# Image.net
KiCad netlist of a schematic drawn in Altium Designer
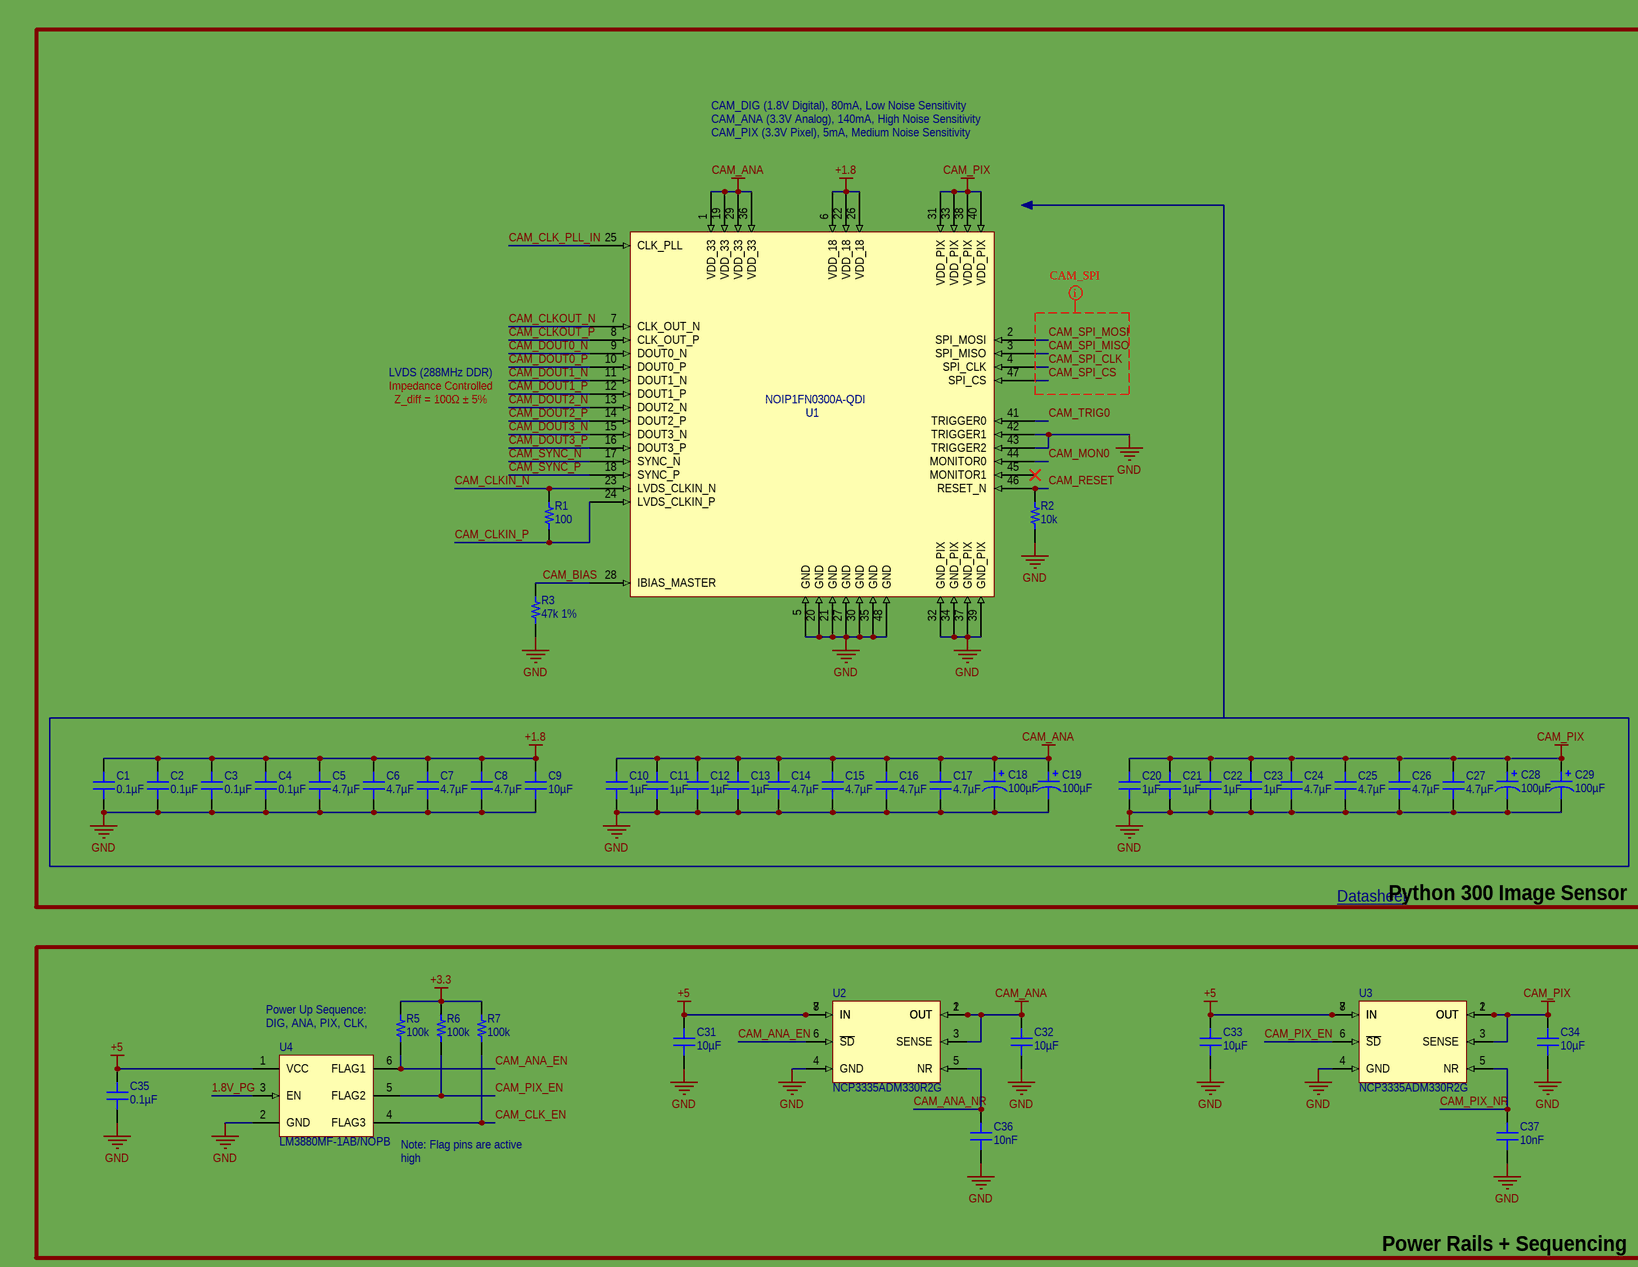
[diagram p0: Image.SchDoc, left]
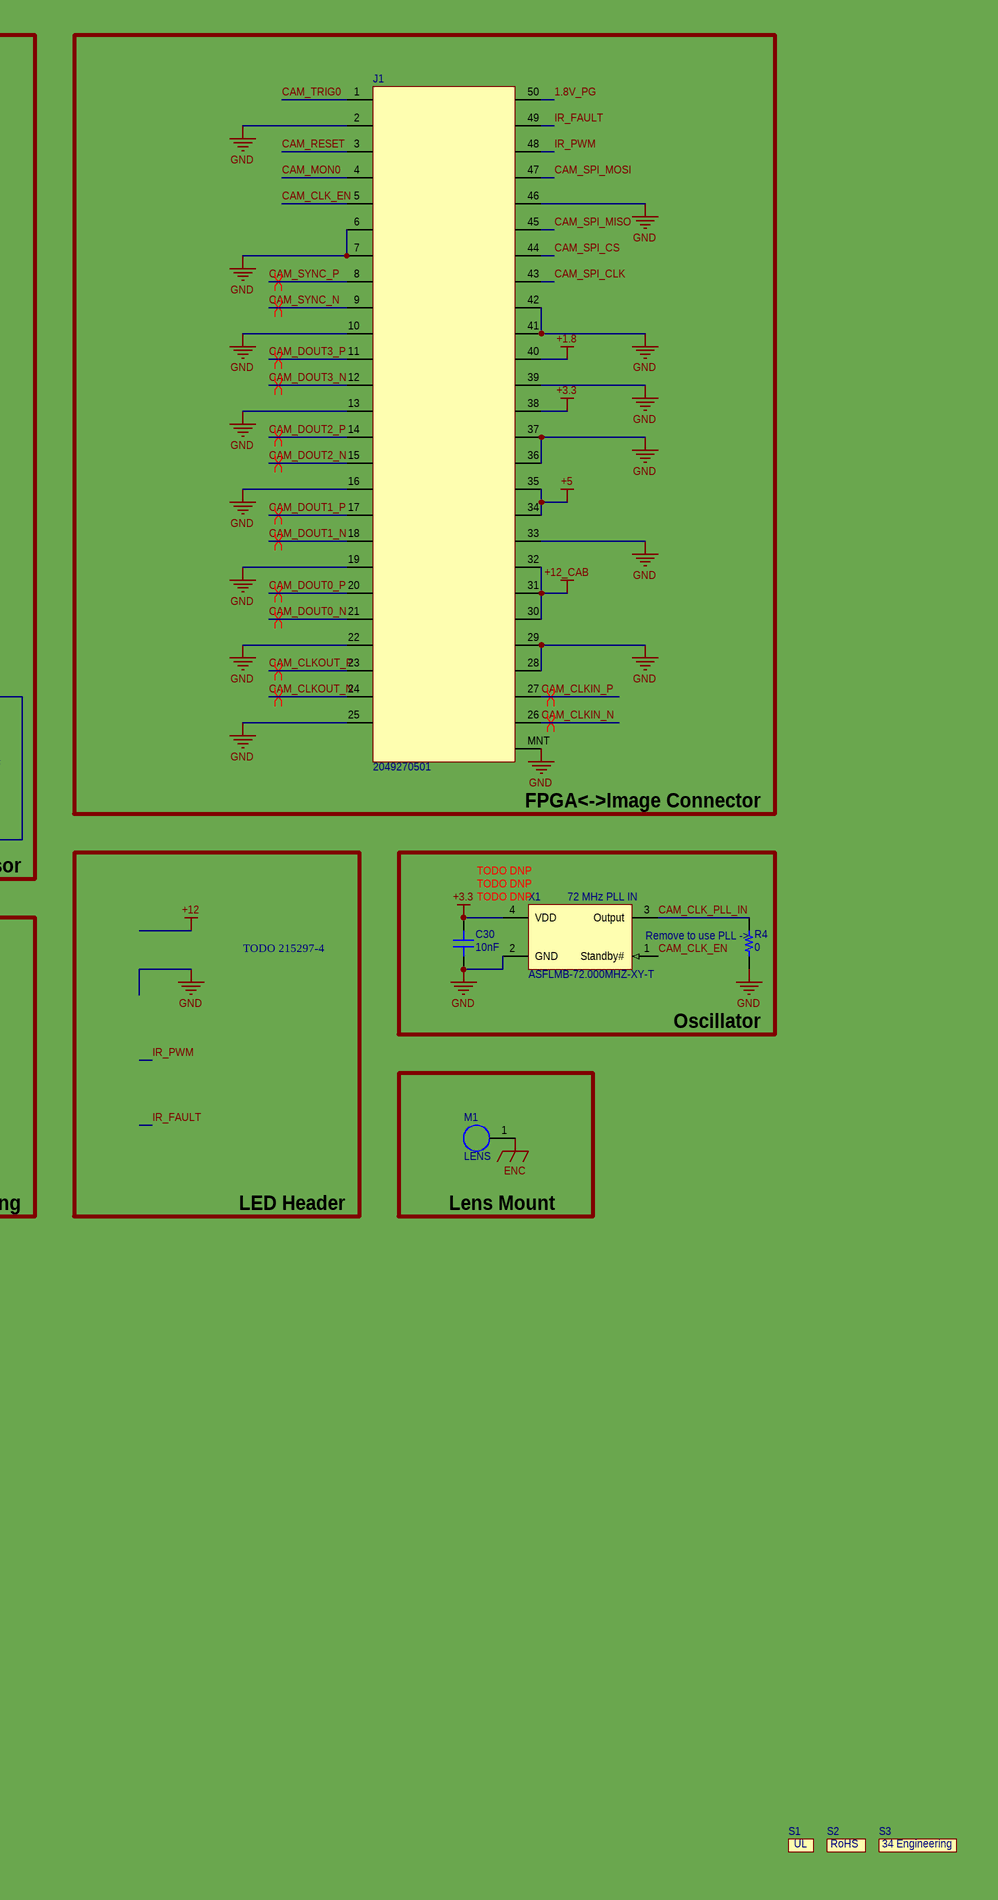
[diagram p1: Image.SchDoc, right]

(export (version "E")
  (design (tool "Eeschema 10.0.6"))
  (components
    (comp (ref "C1")
      (value "0.1µF")
      (footprint "CAP 0402_1005")
      (description "CAP CER 0.1UF 10V X7R 0402")
      (fields (field (name "PART NUMBER") "0402ZC104KAT2A") (field (name "MANUFACTURER") "AVX Corporation"))
      (libsource (lib "altium_library") (part "Capacitor"))
    )
    (comp (ref "C2")
      (value "0.1µF")
      (footprint "CAP 0402_1005")
      (description "CAP CER 0.1UF 10V X7R 0402")
      (fields (field (name "PART NUMBER") "0402ZC104KAT2A") (field (name "MANUFACTURER") "AVX Corporation"))
      (libsource (lib "altium_library") (part "Capacitor"))
    )
    (comp (ref "C3")
      (value "0.1µF")
      (footprint "CAP 0402_1005")
      (description "CAP CER 0.1UF 10V X7R 0402")
      (fields (field (name "PART NUMBER") "0402ZC104KAT2A") (field (name "MANUFACTURER") "AVX Corporation"))
      (libsource (lib "altium_library") (part "Capacitor"))
    )
    (comp (ref "C4")
      (value "0.1µF")
      (footprint "CAP 0402_1005")
      (description "CAP CER 0.1UF 10V X7R 0402")
      (fields (field (name "PART NUMBER") "0402ZC104KAT2A") (field (name "MANUFACTURER") "AVX Corporation"))
      (libsource (lib "altium_library") (part "Capacitor"))
    )
    (comp (ref "C5")
      (value "4.7µF")
      (footprint "CAP 0402_1005")
      (description "CAP CER 4.7UF 6.3V X5R 0402")
      (fields (field (name "PART NUMBER") "04026D475MAT2A") (field (name "MANUFACTURER") "AVX Corporation"))
      (libsource (lib "altium_library") (part "Capacitor"))
    )
    (comp (ref "C6")
      (value "4.7µF")
      (footprint "CAP 0402_1005")
      (description "CAP CER 4.7UF 6.3V X5R 0402")
      (fields (field (name "PART NUMBER") "04026D475MAT2A") (field (name "MANUFACTURER") "AVX Corporation"))
      (libsource (lib "altium_library") (part "Capacitor"))
    )
    (comp (ref "C7")
      (value "4.7µF")
      (footprint "CAP 0402_1005")
      (description "CAP CER 4.7UF 6.3V X5R 0402")
      (fields (field (name "PART NUMBER") "04026D475MAT2A") (field (name "MANUFACTURER") "AVX Corporation"))
      (libsource (lib "altium_library") (part "Capacitor"))
    )
    (comp (ref "C8")
      (value "4.7µF")
      (footprint "CAP 0402_1005")
      (description "CAP CER 4.7UF 6.3V X5R 0402")
      (fields (field (name "PART NUMBER") "04026D475MAT2A") (field (name "MANUFACTURER") "AVX Corporation"))
      (libsource (lib "altium_library") (part "Capacitor"))
    )
    (comp (ref "C9")
      (value "10µF")
      (footprint "CAP 0603_1608")
      (description "CAP CER 10UF 6.3V X5R 0603")
      (fields
        (field (name "PART NUMBER") "CL10A106MQ8NNNC")
        (field (name "MANUFACTURER") "Samsung Electro-Mechanics")
      )
      (libsource (lib "altium_library") (part "Capacitor"))
    )
    (comp (ref "C10")
      (value "1µF")
      (footprint "CAP 0402_1005")
      (description "CAP CER 1UF 6.3V X5R 0402")
      (fields (field (name "PART NUMBER") "C0402C105K9PAC7800") (field (name "MANUFACTURER") "KEMET"))
      (libsource (lib "altium_library") (part "Capacitor"))
    )
    (comp (ref "C11")
      (value "1µF")
      (footprint "CAP 0402_1005")
      (description "CAP CER 1UF 6.3V X5R 0402")
      (fields (field (name "PART NUMBER") "C0402C105K9PAC7800") (field (name "MANUFACTURER") "KEMET"))
      (libsource (lib "altium_library") (part "Capacitor"))
    )
    (comp (ref "C12")
      (value "1µF")
      (footprint "CAP 0402_1005")
      (description "CAP CER 1UF 6.3V X5R 0402")
      (fields (field (name "PART NUMBER") "C0402C105K9PAC7800") (field (name "MANUFACTURER") "KEMET"))
      (libsource (lib "altium_library") (part "Capacitor"))
    )
    (comp (ref "C13")
      (value "1µF")
      (footprint "CAP 0402_1005")
      (description "CAP CER 1UF 6.3V X5R 0402")
      (fields (field (name "PART NUMBER") "C0402C105K9PAC7800") (field (name "MANUFACTURER") "KEMET"))
      (libsource (lib "altium_library") (part "Capacitor"))
    )
    (comp (ref "C14")
      (value "4.7µF")
      (footprint "CAP 0402_1005")
      (description "CAP CER 4.7UF 6.3V X5R 0402")
      (fields (field (name "PART NUMBER") "04026D475MAT2A") (field (name "MANUFACTURER") "AVX Corporation"))
      (libsource (lib "altium_library") (part "Capacitor"))
    )
    (comp (ref "C15")
      (value "4.7µF")
      (footprint "CAP 0402_1005")
      (description "CAP CER 4.7UF 6.3V X5R 0402")
      (fields (field (name "PART NUMBER") "04026D475MAT2A") (field (name "MANUFACTURER") "AVX Corporation"))
      (libsource (lib "altium_library") (part "Capacitor"))
    )
    (comp (ref "C16")
      (value "4.7µF")
      (footprint "CAP 0402_1005")
      (description "CAP CER 4.7UF 6.3V X5R 0402")
      (fields (field (name "PART NUMBER") "04026D475MAT2A") (field (name "MANUFACTURER") "AVX Corporation"))
      (libsource (lib "altium_library") (part "Capacitor"))
    )
    (comp (ref "C17")
      (value "4.7µF")
      (footprint "CAP 0402_1005")
      (description "CAP CER 4.7UF 6.3V X5R 0402")
      (fields (field (name "PART NUMBER") "04026D475MAT2A") (field (name "MANUFACTURER") "AVX Corporation"))
      (libsource (lib "altium_library") (part "Capacitor"))
    )
    (comp (ref "C18")
      (value "100µF")
      (footprint "CAP POL 1411_3528")
      (description "CAP TANT 100UF 20% 10V 1411")
      (fields (field (name "PART NUMBER") "TPSB107M010R0400") (field (name "MANUFACTURER") "AVX Corporation"))
      (libsource (lib "altium_library") (part "Polarised Capacitor"))
    )
    (comp (ref "C19")
      (value "100µF")
      (footprint "CAP POL 1411_3528")
      (description "CAP TANT 100UF 20% 10V 1411")
      (fields (field (name "PART NUMBER") "TPSB107M010R0400") (field (name "MANUFACTURER") "AVX Corporation"))
      (libsource (lib "altium_library") (part "Polarised Capacitor"))
    )
    (comp (ref "C20")
      (value "1µF")
      (footprint "CAP 0402_1005")
      (description "CAP CER 1UF 6.3V X5R 0402")
      (fields (field (name "PART NUMBER") "C0402C105K9PAC7800") (field (name "MANUFACTURER") "KEMET"))
      (libsource (lib "altium_library") (part "Capacitor"))
    )
    (comp (ref "C21")
      (value "1µF")
      (footprint "CAP 0402_1005")
      (description "CAP CER 1UF 6.3V X5R 0402")
      (fields (field (name "PART NUMBER") "C0402C105K9PAC7800") (field (name "MANUFACTURER") "KEMET"))
      (libsource (lib "altium_library") (part "Capacitor"))
    )
    (comp (ref "C22")
      (value "1µF")
      (footprint "CAP 0402_1005")
      (description "CAP CER 1UF 6.3V X5R 0402")
      (fields (field (name "PART NUMBER") "C0402C105K9PAC7800") (field (name "MANUFACTURER") "KEMET"))
      (libsource (lib "altium_library") (part "Capacitor"))
    )
    (comp (ref "C23")
      (value "1µF")
      (footprint "CAP 0402_1005")
      (description "CAP CER 1UF 6.3V X5R 0402")
      (fields (field (name "PART NUMBER") "C0402C105K9PAC7800") (field (name "MANUFACTURER") "KEMET"))
      (libsource (lib "altium_library") (part "Capacitor"))
    )
    (comp (ref "C24")
      (value "4.7µF")
      (footprint "CAP 0402_1005")
      (description "CAP CER 4.7UF 6.3V X5R 0402")
      (fields (field (name "PART NUMBER") "04026D475MAT2A") (field (name "MANUFACTURER") "AVX Corporation"))
      (libsource (lib "altium_library") (part "Capacitor"))
    )
    (comp (ref "C25")
      (value "4.7µF")
      (footprint "CAP 0402_1005")
      (description "CAP CER 4.7UF 6.3V X5R 0402")
      (fields (field (name "PART NUMBER") "04026D475MAT2A") (field (name "MANUFACTURER") "AVX Corporation"))
      (libsource (lib "altium_library") (part "Capacitor"))
    )
    (comp (ref "C26")
      (value "4.7µF")
      (footprint "CAP 0402_1005")
      (description "CAP CER 4.7UF 6.3V X5R 0402")
      (fields (field (name "PART NUMBER") "04026D475MAT2A") (field (name "MANUFACTURER") "AVX Corporation"))
      (libsource (lib "altium_library") (part "Capacitor"))
    )
    (comp (ref "C27")
      (value "4.7µF")
      (footprint "CAP 0402_1005")
      (description "CAP CER 4.7UF 6.3V X5R 0402")
      (fields (field (name "PART NUMBER") "04026D475MAT2A") (field (name "MANUFACTURER") "AVX Corporation"))
      (libsource (lib "altium_library") (part "Capacitor"))
    )
    (comp (ref "C28")
      (value "100µF")
      (footprint "CAP POL 1411_3528")
      (description "CAP TANT 100UF 20% 10V 1411")
      (fields (field (name "PART NUMBER") "TPSB107M010R0400") (field (name "MANUFACTURER") "AVX Corporation"))
      (libsource (lib "altium_library") (part "Polarised Capacitor"))
    )
    (comp (ref "C29")
      (value "100µF")
      (footprint "CAP POL 1411_3528")
      (description "CAP TANT 100UF 20% 10V 1411")
      (fields (field (name "PART NUMBER") "TPSB107M010R0400") (field (name "MANUFACTURER") "AVX Corporation"))
      (libsource (lib "altium_library") (part "Polarised Capacitor"))
    )
    (comp (ref "C30")
      (value "10nF")
      (footprint "CAP 0402_1005")
      (description "CAP CER 10000PF 6.3V X7R 0402")
      (fields
        (field (name "PART NUMBER") "0402B103K6R3CT")
        (field (name "MANUFACTURER") "Walsin Technology Corporation")
      )
      (libsource (lib "altium_library") (part "Capacitor"))
    )
    (comp (ref "C31")
      (value "10µF")
      (footprint "CAP 0402_1005")
      (description "CAP CER 10UF 10V X5R 0402")
      (fields (field (name "PART NUMBER") "0402ZD106MAT2A") (field (name "MANUFACTURER") "AVX Corporation"))
      (libsource (lib "altium_library") (part "Capacitor"))
    )
    (comp (ref "C32")
      (value "10µF")
      (footprint "CAP 0402_1005")
      (description "CAP CER 10UF 10V X5R 0402")
      (fields (field (name "PART NUMBER") "0402ZD106MAT2A") (field (name "MANUFACTURER") "AVX Corporation"))
      (libsource (lib "altium_library") (part "Capacitor"))
    )
    (comp (ref "C33")
      (value "10µF")
      (footprint "CAP 0402_1005")
      (description "CAP CER 10UF 10V X5R 0402")
      (fields (field (name "PART NUMBER") "0402ZD106MAT2A") (field (name "MANUFACTURER") "AVX Corporation"))
      (libsource (lib "altium_library") (part "Capacitor"))
    )
    (comp (ref "C34")
      (value "10µF")
      (footprint "CAP 0402_1005")
      (description "CAP CER 10UF 10V X5R 0402")
      (fields (field (name "PART NUMBER") "0402ZD106MAT2A") (field (name "MANUFACTURER") "AVX Corporation"))
      (libsource (lib "altium_library") (part "Capacitor"))
    )
    (comp (ref "C35")
      (value "0.1µF")
      (footprint "CAP 0402_1005")
      (description "CAP CER 0.1UF 10V X7R 0402")
      (fields (field (name "PART NUMBER") "0402ZC104KAT2A") (field (name "MANUFACTURER") "AVX Corporation"))
      (libsource (lib "altium_library") (part "Capacitor"))
    )
    (comp (ref "C36")
      (value "10nF")
      (footprint "CAP 0402_1005")
      (description "CAP CER 10000PF 6.3V X7R 0402")
      (fields
        (field (name "PART NUMBER") "0402B103K6R3CT")
        (field (name "MANUFACTURER") "Walsin Technology Corporation")
      )
      (libsource (lib "altium_library") (part "Capacitor"))
    )
    (comp (ref "C37")
      (value "10nF")
      (footprint "CAP 0402_1005")
      (description "CAP CER 10000PF 6.3V X7R 0402")
      (fields
        (field (name "PART NUMBER") "0402B103K6R3CT")
        (field (name "MANUFACTURER") "Walsin Technology Corporation")
      )
      (libsource (lib "altium_library") (part "Capacitor"))
    )
    (comp (ref "J1")
      (value "2049270501")
      (footprint "2049270501")
      (fields (field (name "MANUFACTURER") "Molex") (field (name "MANUFACTURER PART NUMBER") "203955-0503"))
      (libsource (lib "Virtex") (part "2049270501"))
    )
    (comp (ref "M1")
      (value "LENS")
      (footprint "LENS_MNT")
      (description "Virtex Python 300 Lens Mount 34V0-LN-MNT")
      (libsource (lib "Virtex") (part "LENS_MNT"))
    )
    (comp (ref "R1")
      (value "100")
      (footprint "RES 0402_1005")
      (description "RES SMD 100 OHM 1% 1/16W 0402")
      (fields
        (field (name "PART NUMBER") "CRG0402F100R")
        (field (name "MANUFACTURER") "TE Connectivity Passive Product")
      )
      (libsource (lib "altium_library") (part "Resistor"))
    )
    (comp (ref "R2")
      (value "10k")
      (footprint "RES 0402_1005")
      (description "RES SMD 10K OHM 1% 1/10W 0402")
      (fields
        (field (name "PART NUMBER") "MCS0402MC1002FE000")
        (field (name "MANUFACTURER") "Vishay Beyschlag")
      )
      (libsource (lib "altium_library") (part "Resistor"))
    )
    (comp (ref "R3")
      (value "47k 1%")
      (footprint "RES 0402_1005")
      (description "RES 47K OHM 1% 1/16W 0402")
      (fields
        (field (name "PART NUMBER") "RMCF0402FT47K0")
        (field (name "MANUFACTURER") "Stackpole Electronics Inc")
      )
      (libsource (lib "altium_library") (part "Resistor"))
    )
    (comp (ref "R4")
      (value "0")
      (footprint "RES 0603_1608")
      (description "RES SMD 0 OHM JUMPER 1/3W 0603")
      (fields (field (name "PART NUMBER") "CRCW06030000Z0EAHP") (field (name "MANUFACTURER") "Vishay Dale"))
      (libsource (lib "altium_library") (part "Resistor"))
    )
    (comp (ref "R5")
      (value "100k")
      (footprint "RES 0402_1005")
      (description "RES SMD 100K OHM 1% 1/10W 0402")
      (fields
        (field (name "PART NUMBER") "MCS04020C1003FE000")
        (field (name "MANUFACTURER") "Vishay Beyschlag")
      )
      (libsource (lib "altium_library") (part "Resistor"))
    )
    (comp (ref "R6")
      (value "100k")
      (footprint "RES 0402_1005")
      (description "RES SMD 100K OHM 1% 1/10W 0402")
      (fields
        (field (name "PART NUMBER") "MCS04020C1003FE000")
        (field (name "MANUFACTURER") "Vishay Beyschlag")
      )
      (libsource (lib "altium_library") (part "Resistor"))
    )
    (comp (ref "R7")
      (value "100k")
      (footprint "RES 0402_1005")
      (description "RES SMD 100K OHM 1% 1/10W 0402")
      (fields
        (field (name "PART NUMBER") "MCS04020C1003FE000")
        (field (name "MANUFACTURER") "Vishay Beyschlag")
      )
      (libsource (lib "altium_library") (part "Resistor"))
    )
    (comp (ref "S1") (value "~") (footprint "UL") (libsource (lib "Virtex") (part "UL")))
    (comp (ref "S2") (value "~") (footprint "RoHS") (libsource (lib "Virtex") (part "RoHS")))
    (comp (ref "S3")
      (value "~")
      (footprint "34EngineeringLogo")
      (description "34 Engineering Silkscreen Logo")
      (libsource (lib "Virtex") (part "34EngineeringLogo"))
    )
    (comp (ref "U1")
      (value "NOIP1FN0300A-QDI")
      (footprint "NOIP1FN0300A-QDI")
      (description "IC IMAGE SENSOR 0.3MP 48LCC")
      (fields (field (name "MANUFACTURER") "ON Semiconductor"))
      (libsource (lib "Virtex") (part "NOIP1FN0300A-QDI"))
    )
    (comp (ref "U2")
      (value "NCP3335ADM330R2G")
      (footprint "NCP3335ADM330R2G")
      (description "Linear Voltage Regulator, LDO, Ultra High Accuracy, Low Iq, 500 mA, V out : 3.3 V")
      (fields (field (name "MANUFACTURER") "ON Semiconductor"))
      (libsource (lib "Virtex") (part "NCP3335ADM330R2G"))
    )
    (comp (ref "U3")
      (value "NCP3335ADM330R2G")
      (footprint "NCP3335ADM330R2G")
      (description "Linear Voltage Regulator, LDO, Ultra High Accuracy, Low Iq, 500 mA, V out : 3.3 V")
      (fields (field (name "MANUFACTURER") "ON Semiconductor"))
      (libsource (lib "Virtex") (part "NCP3335ADM330R2G"))
    )
    (comp (ref "U4")
      (value "LM3880MF-1AB/NOPB")
      (footprint "DBV0006A_M")
      (description "Power Sequencer, 6-pin SOT-23, Pb-Free, 1000 Reel")
      (fields (field (name "MANUFACTURER") "Texas Instruments"))
      (libsource (lib "Altium Content Vault") (part "PM-CNTL-LM3880-6"))
    )
    (comp (ref "X1")
      (value "ASFLMB-72.000MHZ-XY-T")
      (footprint "ASFLMB-72.000MHZ-XY-T")
      (description "Silicon Oscillator 72MHz 15pF ±10ppm 4-Pin QFN T/R")
      (fields (field (name "MANUFACTURER") "Abracon"))
      (libsource (lib "Virtex") (part "ASFLMB-72.000MHZ-XY-T"))
    )
  )
  (nets
    (net (code "1") (name "+1.8") (class "Default")
      (node (ref "C1") (pin "2") (pinfunction "2_2") (pintype "passive"))
      (node (ref "C2") (pin "2") (pinfunction "2_2") (pintype "passive"))
      (node (ref "C3") (pin "2") (pinfunction "2_2") (pintype "passive"))
      (node (ref "C4") (pin "2") (pinfunction "2_2") (pintype "passive"))
      (node (ref "C5") (pin "2") (pinfunction "2_2") (pintype "passive"))
      (node (ref "C6") (pin "2") (pinfunction "2_2") (pintype "passive"))
      (node (ref "C7") (pin "2") (pinfunction "2_2") (pintype "passive"))
      (node (ref "C8") (pin "2") (pinfunction "2_2") (pintype "passive"))
      (node (ref "C9") (pin "2") (pinfunction "2_2") (pintype "passive"))
      (node (ref "J1") (pin "40") (pintype "passive"))
      (node (ref "U1") (pin "22") (pinfunction "VDD_18_22") (pintype "input"))
      (node (ref "U1") (pin "26") (pinfunction "VDD_18_26") (pintype "input"))
      (node (ref "U1") (pin "6") (pinfunction "VDD_18_6") (pintype "input"))
    )
    (net (code "2") (name "+3.3") (class "Default")
      (node (ref "C30") (pin "2") (pinfunction "2_2") (pintype "passive"))
      (node (ref "J1") (pin "38") (pintype "passive"))
      (node (ref "R5") (pin "2") (pinfunction "2_2") (pintype "passive"))
      (node (ref "R6") (pin "2") (pinfunction "2_2") (pintype "passive"))
      (node (ref "R7") (pin "2") (pinfunction "2_2") (pintype "passive"))
      (node (ref "X1") (pin "4") (pinfunction "VDD_4") (pintype "power_in"))
    )
    (net (code "3") (name "+5") (class "Default")
      (node (ref "C31") (pin "2") (pinfunction "2_2") (pintype "passive"))
      (node (ref "C33") (pin "2") (pinfunction "2_2") (pintype "passive"))
      (node (ref "C35") (pin "2") (pinfunction "2_2") (pintype "passive"))
      (node (ref "J1") (pin "34") (pintype "passive"))
      (node (ref "J1") (pin "35") (pintype "passive"))
      (node (ref "U2") (pin "7") (pinfunction "IN_7") (pintype "input"))
      (node (ref "U2") (pin "8") (pinfunction "IN_8") (pintype "input"))
      (node (ref "U3") (pin "7") (pinfunction "IN_7") (pintype "input"))
      (node (ref "U3") (pin "8") (pinfunction "IN_8") (pintype "input"))
      (node (ref "U4") (pin "1") (pinfunction "VCC_1") (pintype "power_in"))
    )
    (net (code "5") (name "+12_CAB") (class "Default")
      (node (ref "J1") (pin "30") (pintype "passive"))
      (node (ref "J1") (pin "31") (pintype "passive"))
      (node (ref "J1") (pin "32") (pintype "passive"))
    )
    (net (code "6") (name "/1.8V_PG") (class "Default")
      (node (ref "J1") (pin "50") (pintype "passive"))
      (node (ref "U4") (pin "3") (pinfunction "EN_3") (pintype "input"))
    )
    (net (code "7") (name "/CAM_ANA_EN") (class "Default")
      (node (ref "R5") (pin "1") (pinfunction "1_1") (pintype "passive"))
      (node (ref "U2") (pin "6") (pinfunction "~{SD}_6") (pintype "input"))
      (node (ref "U4") (pin "6") (pinfunction "FLAG1_6") (pintype "open_collector"))
    )
    (net (code "8") (name "/CAM_ANA_NR") (class "Default")
      (node (ref "C36") (pin "2") (pinfunction "2_2") (pintype "passive"))
      (node (ref "U2") (pin "5") (pinfunction "NR_5") (pintype "input"))
    )
    (net (code "9") (name "/CAM_BIAS") (class "Default")
      (node (ref "R3") (pin "2") (pinfunction "2_2") (pintype "passive"))
      (node (ref "U1") (pin "28") (pinfunction "IBIAS_MASTER_28") (pintype "input"))
    )
    (net (code "10") (name "/CAM_CLKIN_N") (class "Default")
      (node (ref "J1") (pin "26") (pintype "passive"))
      (node (ref "R1") (pin "2") (pinfunction "2_2") (pintype "passive"))
      (node (ref "U1") (pin "23") (pinfunction "LVDS_CLKIN_N_23") (pintype "input"))
    )
    (net (code "11") (name "/CAM_CLKIN_P") (class "Default")
      (node (ref "J1") (pin "27") (pintype "passive"))
      (node (ref "R1") (pin "1") (pinfunction "1_1") (pintype "passive"))
      (node (ref "U1") (pin "24") (pinfunction "LVDS_CLKIN_P_24") (pintype "input"))
    )
    (net (code "12") (name "/CAM_CLKOUT_N") (class "Default")
      (node (ref "J1") (pin "24") (pintype "passive"))
      (node (ref "U1") (pin "7") (pinfunction "CLK_OUT_N_7") (pintype "input"))
    )
    (net (code "13") (name "/CAM_CLKOUT_P") (class "Default")
      (node (ref "J1") (pin "23") (pintype "passive"))
      (node (ref "U1") (pin "8") (pinfunction "CLK_OUT_P_8") (pintype "input"))
    )
    (net (code "14") (name "/CAM_CLK_EN") (class "Default")
      (node (ref "J1") (pin "5") (pintype "passive"))
      (node (ref "R7") (pin "1") (pinfunction "1_1") (pintype "passive"))
      (node (ref "U4") (pin "4") (pinfunction "FLAG3_4") (pintype "open_collector"))
      (node (ref "X1") (pin "1") (pinfunction "Standby#_1") (pintype "input"))
    )
    (net (code "15") (name "/CAM_CLK_PLL_IN") (class "Default")
      (node (ref "R4") (pin "2") (pinfunction "2_2") (pintype "passive"))
      (node (ref "U1") (pin "25") (pinfunction "CLK_PLL_25") (pintype "input"))
      (node (ref "X1") (pin "3") (pinfunction "Output_3") (pintype "power_in"))
    )
    (net (code "16") (name "/CAM_DOUT0_N") (class "Default")
      (node (ref "J1") (pin "21") (pintype "passive"))
      (node (ref "U1") (pin "9") (pinfunction "DOUT0_N_9") (pintype "input"))
    )
    (net (code "17") (name "/CAM_DOUT0_P") (class "Default")
      (node (ref "J1") (pin "20") (pintype "passive"))
      (node (ref "U1") (pin "10") (pinfunction "DOUT0_P_10") (pintype "input"))
    )
    (net (code "18") (name "/CAM_DOUT1_N") (class "Default")
      (node (ref "J1") (pin "18") (pintype "passive"))
      (node (ref "U1") (pin "11") (pinfunction "DOUT1_N_11") (pintype "input"))
    )
    (net (code "19") (name "/CAM_DOUT1_P") (class "Default")
      (node (ref "J1") (pin "17") (pintype "passive"))
      (node (ref "U1") (pin "12") (pinfunction "DOUT1_P_12") (pintype "input"))
    )
    (net (code "20") (name "/CAM_DOUT2_N") (class "Default")
      (node (ref "J1") (pin "15") (pintype "passive"))
      (node (ref "U1") (pin "13") (pinfunction "DOUT2_N_13") (pintype "input"))
    )
    (net (code "21") (name "/CAM_DOUT2_P") (class "Default")
      (node (ref "J1") (pin "14") (pintype "passive"))
      (node (ref "U1") (pin "14") (pinfunction "DOUT2_P_14") (pintype "input"))
    )
    (net (code "22") (name "/CAM_DOUT3_N") (class "Default")
      (node (ref "J1") (pin "12") (pintype "passive"))
      (node (ref "U1") (pin "15") (pinfunction "DOUT3_N_15") (pintype "input"))
    )
    (net (code "23") (name "/CAM_DOUT3_P") (class "Default")
      (node (ref "J1") (pin "11") (pintype "passive"))
      (node (ref "U1") (pin "16") (pinfunction "DOUT3_P_16") (pintype "input"))
    )
    (net (code "24") (name "/CAM_MON0") (class "Default")
      (node (ref "J1") (pin "4") (pintype "passive"))
      (node (ref "U1") (pin "44") (pinfunction "MONITOR0_44") (pintype "input"))
    )
    (net (code "25") (name "/CAM_PIX_EN") (class "Default")
      (node (ref "R6") (pin "1") (pinfunction "1_1") (pintype "passive"))
      (node (ref "U3") (pin "6") (pinfunction "~{SD}_6") (pintype "input"))
      (node (ref "U4") (pin "5") (pinfunction "FLAG2_5") (pintype "open_collector"))
    )
    (net (code "26") (name "/CAM_PIX_NR") (class "Default")
      (node (ref "C37") (pin "2") (pinfunction "2_2") (pintype "passive"))
      (node (ref "U3") (pin "5") (pinfunction "NR_5") (pintype "input"))
    )
    (net (code "27") (name "/CAM_RESET") (class "Default")
      (node (ref "J1") (pin "3") (pintype "passive"))
      (node (ref "R2") (pin "2") (pinfunction "2_2") (pintype "passive"))
      (node (ref "U1") (pin "46") (pinfunction "RESET_N_46") (pintype "input"))
    )
    (net (code "28") (name "/CAM_SPI_CLK") (class "Default")
      (node (ref "J1") (pin "43") (pintype "passive"))
      (node (ref "U1") (pin "4") (pinfunction "SPI_CLK_4") (pintype "input"))
    )
    (net (code "29") (name "/CAM_SPI_CS") (class "Default")
      (node (ref "J1") (pin "44") (pintype "passive"))
      (node (ref "U1") (pin "47") (pinfunction "SPI_CS_47") (pintype "input"))
    )
    (net (code "30") (name "/CAM_SPI_MISO") (class "Default")
      (node (ref "J1") (pin "45") (pintype "passive"))
      (node (ref "U1") (pin "3") (pinfunction "SPI_MISO_3") (pintype "input"))
    )
    (net (code "31") (name "/CAM_SPI_MOSI") (class "Default")
      (node (ref "J1") (pin "47") (pintype "passive"))
      (node (ref "U1") (pin "2") (pinfunction "SPI_MOSI_2") (pintype "input"))
    )
    (net (code "32") (name "/CAM_SYNC_N") (class "Default")
      (node (ref "J1") (pin "9") (pintype "passive"))
      (node (ref "U1") (pin "17") (pinfunction "SYNC_N_17") (pintype "input"))
    )
    (net (code "33") (name "/CAM_SYNC_P") (class "Default")
      (node (ref "J1") (pin "8") (pintype "passive"))
      (node (ref "U1") (pin "18") (pinfunction "SYNC_P_18") (pintype "input"))
    )
    (net (code "34") (name "/CAM_TRIG0") (class "Default")
      (node (ref "J1") (pin "1") (pintype "passive"))
      (node (ref "U1") (pin "41") (pinfunction "TRIGGER0_41") (pintype "input"))
    )
    (net (code "35") (name "/IR_FAULT") (class "Default") (node (ref "J1") (pin "49") (pintype "passive")))
    (net (code "36") (name "/IR_PWM") (class "Default") (node (ref "J1") (pin "48") (pintype "passive")))
    (net (code "37") (name "CAM_ANA") (class "Default")
      (node (ref "C10") (pin "2") (pinfunction "2_2") (pintype "passive"))
      (node (ref "C11") (pin "2") (pinfunction "2_2") (pintype "passive"))
      (node (ref "C12") (pin "2") (pinfunction "2_2") (pintype "passive"))
      (node (ref "C13") (pin "2") (pinfunction "2_2") (pintype "passive"))
      (node (ref "C14") (pin "2") (pinfunction "2_2") (pintype "passive"))
      (node (ref "C15") (pin "2") (pinfunction "2_2") (pintype "passive"))
      (node (ref "C16") (pin "2") (pinfunction "2_2") (pintype "passive"))
      (node (ref "C17") (pin "2") (pinfunction "2_2") (pintype "passive"))
      (node (ref "C18") (pin "1") (pinfunction "1_1") (pintype "passive"))
      (node (ref "C19") (pin "1") (pinfunction "1_1") (pintype "passive"))
      (node (ref "C32") (pin "2") (pinfunction "2_2") (pintype "passive"))
      (node (ref "U1") (pin "1") (pinfunction "VDD_33_1") (pintype "input"))
      (node (ref "U1") (pin "19") (pinfunction "VDD_33_19") (pintype "input"))
      (node (ref "U1") (pin "29") (pinfunction "VDD_33_29") (pintype "input"))
      (node (ref "U1") (pin "36") (pinfunction "VDD_33_36") (pintype "input"))
      (node (ref "U2") (pin "1") (pinfunction "OUT_1") (pintype "input"))
      (node (ref "U2") (pin "2") (pinfunction "OUT_2") (pintype "input"))
      (node (ref "U2") (pin "3") (pinfunction "SENSE_3") (pintype "input"))
    )
    (net (code "38") (name "CAM_PIX") (class "Default")
      (node (ref "C20") (pin "2") (pinfunction "2_2") (pintype "passive"))
      (node (ref "C21") (pin "2") (pinfunction "2_2") (pintype "passive"))
      (node (ref "C22") (pin "2") (pinfunction "2_2") (pintype "passive"))
      (node (ref "C23") (pin "2") (pinfunction "2_2") (pintype "passive"))
      (node (ref "C24") (pin "2") (pinfunction "2_2") (pintype "passive"))
      (node (ref "C25") (pin "2") (pinfunction "2_2") (pintype "passive"))
      (node (ref "C26") (pin "2") (pinfunction "2_2") (pintype "passive"))
      (node (ref "C27") (pin "2") (pinfunction "2_2") (pintype "passive"))
      (node (ref "C28") (pin "1") (pinfunction "1_1") (pintype "passive"))
      (node (ref "C29") (pin "1") (pinfunction "1_1") (pintype "passive"))
      (node (ref "C34") (pin "2") (pinfunction "2_2") (pintype "passive"))
      (node (ref "U1") (pin "31") (pinfunction "VDD_PIX_31") (pintype "input"))
      (node (ref "U1") (pin "33") (pinfunction "VDD_PIX_33") (pintype "input"))
      (node (ref "U1") (pin "38") (pinfunction "VDD_PIX_38") (pintype "input"))
      (node (ref "U1") (pin "40") (pinfunction "VDD_PIX_40") (pintype "input"))
      (node (ref "U3") (pin "1") (pinfunction "OUT_1") (pintype "input"))
      (node (ref "U3") (pin "2") (pinfunction "OUT_2") (pintype "input"))
      (node (ref "U3") (pin "3") (pinfunction "SENSE_3") (pintype "input"))
    )
    (net (code "39") (name "ENC") (class "Default") (node (ref "M1") (pin "1") (pintype "passive")))
    (net (code "40") (name "GND") (class "Default")
      (node (ref "C1") (pin "1") (pinfunction "1_1") (pintype "passive"))
      (node (ref "C10") (pin "1") (pinfunction "1_1") (pintype "passive"))
      (node (ref "C11") (pin "1") (pinfunction "1_1") (pintype "passive"))
      (node (ref "C12") (pin "1") (pinfunction "1_1") (pintype "passive"))
      (node (ref "C13") (pin "1") (pinfunction "1_1") (pintype "passive"))
      (node (ref "C14") (pin "1") (pinfunction "1_1") (pintype "passive"))
      (node (ref "C15") (pin "1") (pinfunction "1_1") (pintype "passive"))
      (node (ref "C16") (pin "1") (pinfunction "1_1") (pintype "passive"))
      (node (ref "C17") (pin "1") (pinfunction "1_1") (pintype "passive"))
      (node (ref "C18") (pin "2") (pinfunction "2_2") (pintype "passive"))
      (node (ref "C19") (pin "2") (pinfunction "2_2") (pintype "passive"))
      (node (ref "C2") (pin "1") (pinfunction "1_1") (pintype "passive"))
      (node (ref "C20") (pin "1") (pinfunction "1_1") (pintype "passive"))
      (node (ref "C21") (pin "1") (pinfunction "1_1") (pintype "passive"))
      (node (ref "C22") (pin "1") (pinfunction "1_1") (pintype "passive"))
      (node (ref "C23") (pin "1") (pinfunction "1_1") (pintype "passive"))
      (node (ref "C24") (pin "1") (pinfunction "1_1") (pintype "passive"))
      (node (ref "C25") (pin "1") (pinfunction "1_1") (pintype "passive"))
      (node (ref "C26") (pin "1") (pinfunction "1_1") (pintype "passive"))
      (node (ref "C27") (pin "1") (pinfunction "1_1") (pintype "passive"))
      (node (ref "C28") (pin "2") (pinfunction "2_2") (pintype "passive"))
      (node (ref "C29") (pin "2") (pinfunction "2_2") (pintype "passive"))
      (node (ref "C3") (pin "1") (pinfunction "1_1") (pintype "passive"))
      (node (ref "C30") (pin "1") (pinfunction "1_1") (pintype "passive"))
      (node (ref "C31") (pin "1") (pinfunction "1_1") (pintype "passive"))
      (node (ref "C32") (pin "1") (pinfunction "1_1") (pintype "passive"))
      (node (ref "C33") (pin "1") (pinfunction "1_1") (pintype "passive"))
      (node (ref "C34") (pin "1") (pinfunction "1_1") (pintype "passive"))
      (node (ref "C35") (pin "1") (pinfunction "1_1") (pintype "passive"))
      (node (ref "C36") (pin "1") (pinfunction "1_1") (pintype "passive"))
      (node (ref "C37") (pin "1") (pinfunction "1_1") (pintype "passive"))
      (node (ref "C4") (pin "1") (pinfunction "1_1") (pintype "passive"))
      (node (ref "C5") (pin "1") (pinfunction "1_1") (pintype "passive"))
      (node (ref "C6") (pin "1") (pinfunction "1_1") (pintype "passive"))
      (node (ref "C7") (pin "1") (pinfunction "1_1") (pintype "passive"))
      (node (ref "C8") (pin "1") (pinfunction "1_1") (pintype "passive"))
      (node (ref "C9") (pin "1") (pinfunction "1_1") (pintype "passive"))
      (node (ref "J1") (pin "10") (pintype "passive"))
      (node (ref "J1") (pin "13") (pintype "passive"))
      (node (ref "J1") (pin "16") (pintype "passive"))
      (node (ref "J1") (pin "19") (pintype "passive"))
      (node (ref "J1") (pin "2") (pintype "passive"))
      (node (ref "J1") (pin "22") (pintype "passive"))
      (node (ref "J1") (pin "25") (pintype "passive"))
      (node (ref "J1") (pin "28") (pintype "passive"))
      (node (ref "J1") (pin "29") (pintype "passive"))
      (node (ref "J1") (pin "33") (pintype "passive"))
      (node (ref "J1") (pin "36") (pintype "passive"))
      (node (ref "J1") (pin "37") (pintype "passive"))
      (node (ref "J1") (pin "39") (pintype "passive"))
      (node (ref "J1") (pin "41") (pintype "passive"))
      (node (ref "J1") (pin "42") (pintype "passive"))
      (node (ref "J1") (pin "46") (pintype "passive"))
      (node (ref "J1") (pin "6") (pintype "passive"))
      (node (ref "J1") (pin "7") (pintype "passive"))
      (node (ref "J1") (pin "MNT") (pintype "passive"))
      (node (ref "R2") (pin "1") (pinfunction "1_1") (pintype "passive"))
      (node (ref "R3") (pin "1") (pinfunction "1_1") (pintype "passive"))
      (node (ref "R4") (pin "1") (pinfunction "1_1") (pintype "passive"))
      (node (ref "U1") (pin "20") (pinfunction "GND_20") (pintype "input"))
      (node (ref "U1") (pin "21") (pinfunction "GND_21") (pintype "input"))
      (node (ref "U1") (pin "27") (pinfunction "GND_27") (pintype "input"))
      (node (ref "U1") (pin "30") (pinfunction "GND_30") (pintype "input"))
      (node (ref "U1") (pin "32") (pinfunction "GND_PIX_32") (pintype "input"))
      (node (ref "U1") (pin "34") (pinfunction "GND_PIX_34") (pintype "input"))
      (node (ref "U1") (pin "35") (pinfunction "GND_35") (pintype "input"))
      (node (ref "U1") (pin "37") (pinfunction "GND_PIX_37") (pintype "input"))
      (node (ref "U1") (pin "39") (pinfunction "GND_PIX_39") (pintype "input"))
      (node (ref "U1") (pin "42") (pinfunction "TRIGGER1_42") (pintype "input"))
      (node (ref "U1") (pin "43") (pinfunction "TRIGGER2_43") (pintype "input"))
      (node (ref "U1") (pin "48") (pinfunction "GND_48") (pintype "input"))
      (node (ref "U1") (pin "5") (pinfunction "GND_5") (pintype "input"))
      (node (ref "U2") (pin "4") (pinfunction "GND_4") (pintype "input"))
      (node (ref "U3") (pin "4") (pinfunction "GND_4") (pintype "input"))
      (node (ref "U4") (pin "2") (pinfunction "GND_2") (pintype "power_in"))
      (node (ref "X1") (pin "2") (pinfunction "GND_2") (pintype "power_in"))
    )
    (net (code "41") (name "unconnected-(U1-MONITOR1-Pad45)") (class "Default")
      (node (ref "U1") (pin "45") (pinfunction "MONITOR1_45") (pintype "input+no_connect"))
    )
  )
)
